# SIM808_RF.net
KiCad netlist of a schematic drawn in Altium Designer
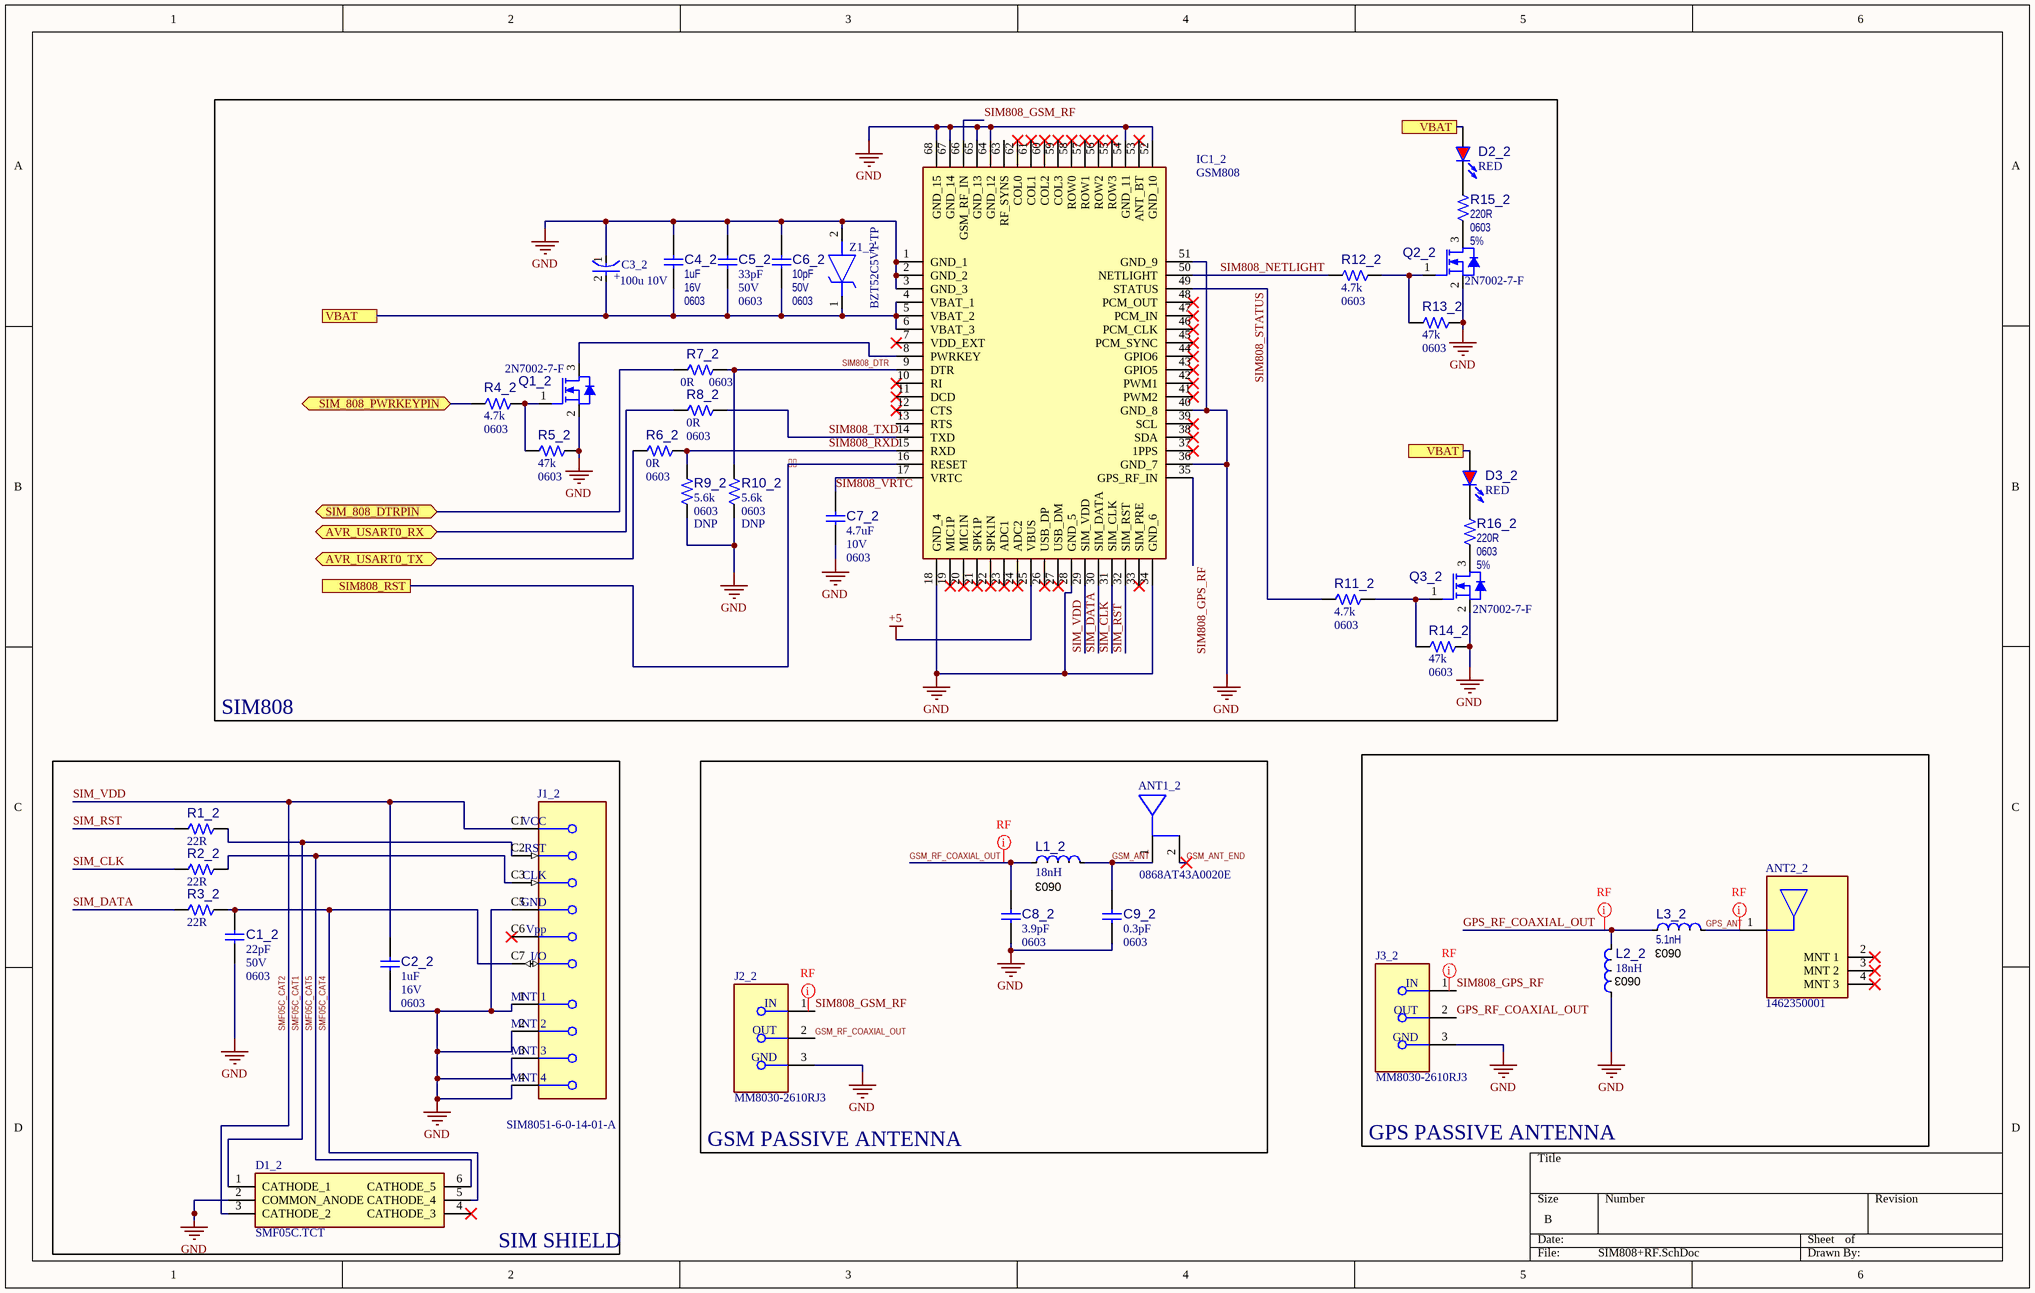
[diagram p0: SIM808+RF.SchDoc]

(export (version "E")
  (design (tool "Eeschema 10.0.6"))
  (components
    (comp (ref "ANT1_2")
      (value "0868AT43A0020E")
      (footprint "FP-0900AT43A0070E-MFG")
      (description "RF ANT CHIP SOLDER SMD")
      (libsource (lib "Altium Content Vault") (part "fdeedc8c81902f4dca238edc9264297"))
    )
    (comp (ref "ANT2_2")
      (value "1462350001")
      (footprint "FP-1462350001-MFG")
      (description "RF ANT 1.575GHZ MOLDED SLDR SMD")
      (fields
        (field (name "OCTOPART") "https://octopart.com/146235-0001-molex-75198029")
        (field (name "MANUFACTURER") "Molex")
      )
      (libsource (lib "Altium Content Vault") (part "44fa71a15c7cd8753818309cfbbf304"))
    )
    (comp (ref "C1_2")
      (value "22pF")
      (footprint "CAP_C_0603")
      (fields
        (field (name "VOLTAGE") "50V")
        (field (name "PACKAGE") "0603")
        (field (name "TOLERANCE") "5%")
        (field (name "Comment") "Capacitor NP")
      )
      (libsource (lib "MCHP-CDB") (part "Capacitor NP"))
    )
    (comp (ref "C2_2")
      (value "1uF")
      (footprint "CAP_C_0603")
      (fields
        (field (name "VOLTAGE") "16V")
        (field (name "PACKAGE") "0603")
        (field (name "TOLERANCE") "10%")
        (field (name "Comment") "Capacitor NP")
      )
      (libsource (lib "MCHP-CDB") (part "Capacitor NP"))
    )
    (comp (ref "C3_2")
      (value "100u 10V")
      (footprint "FP-TAJC-MFG")
      (description "100uF 10V  ±10% 1.2Ω 2312  SMD Tantalum Capacitor")
      (fields (field (name "TOLERANCE") "10%") (field (name "VOLTAGE") "10V"))
      (libsource (lib "Altium Content Vault") (part "203bc49f2ac43e59fd269a8c329ed05"))
    )
    (comp (ref "C4_2")
      (value "1uF")
      (footprint "CAP_C_0603")
      (fields
        (field (name "VOLTAGE") "16V")
        (field (name "PACKAGE") "0603")
        (field (name "TOLERANCE") "10%")
        (field (name "Comment") "Capacitor NP")
      )
      (libsource (lib "MCHP-CDB") (part "Capacitor NP"))
    )
    (comp (ref "C5_2")
      (value "33pF")
      (footprint "CAP_C_0603")
      (fields
        (field (name "VOLTAGE") "50V")
        (field (name "PACKAGE") "0603")
        (field (name "TOLERANCE") "5%")
        (field (name "Comment") "Capacitor NP")
      )
      (libsource (lib "MCHP-CDB") (part "Capacitor NP"))
    )
    (comp (ref "C6_2")
      (value "10pF")
      (footprint "CAP_C_0603")
      (fields
        (field (name "VOLTAGE") "50V")
        (field (name "PACKAGE") "0603")
        (field (name "TOLERANCE") "0.5pF")
        (field (name "Comment") "Capacitor NP")
        (field (name "OWNER") "Leah Whitaker")
      )
      (libsource (lib "MCHP-CDB") (part "Capacitor NP"))
    )
    (comp (ref "C7_2")
      (value "4.7uF")
      (footprint "CAP_C_0603")
      (fields
        (field (name "VOLTAGE") "10V")
        (field (name "PACKAGE") "0603")
        (field (name "TOLERANCE") "80%")
        (field (name "Comment") "Capacitor NP")
      )
      (libsource (lib "MCHP-CDB") (part "Capacitor NP"))
    )
    (comp (ref "C8_2")
      (value "3.9pF")
      (footprint "CAP_C_0603")
      (fields
        (field (name "PACKAGE") "0603")
        (field (name "TOLERANCE") "0.25pF")
        (field (name "Comment") "Capacitor NP")
      )
      (libsource (lib "MCHP-CDB") (part "Capacitor NP"))
    )
    (comp (ref "C9_2")
      (value "0.3pF")
      (footprint "CAP_C_0603")
      (fields
        (field (name "PACKAGE") "0603")
        (field (name "TOLERANCE") "0.25pF")
        (field (name "Comment") "Capacitor NP")
      )
      (libsource (lib "MCHP-CDB") (part "Capacitor NP"))
    )
    (comp (ref "D1_2")
      (value "SMF05C.TCT")
      (footprint "SamacSys:SOT65P210X110-6N")
      (description "TVS Diode (Uni-directional)")
      (fields (field (name "MOUSER PART NUMBER") "947-SMF05C.TCT"))
      (libsource (lib "*") (part "SMF05C.TCT"))
    )
    (comp (ref "D2_2")
      (value "RED")
      (footprint "LED_0603_RED")
      (description "LED")
      (fields (field (name "POWER") "100mW") (field (name "Comment") "LED_red"))
      (libsource (lib "MCHP-CDB") (part "LED_red"))
    )
    (comp (ref "D3_2")
      (value "RED")
      (footprint "LED_0603_RED")
      (description "LED")
      (fields (field (name "POWER") "100mW") (field (name "Comment") "LED_red"))
      (libsource (lib "MCHP-CDB") (part "LED_red"))
    )
    (comp (ref "IC1_2")
      (value "GSM808")
      (footprint "SamacSys:GSM808")
      (description "Integrated Circuit")
      (libsource (lib "*") (part "GSM808"))
    )
    (comp (ref "J1_2")
      (value "SIM8051-6-0-14-01-A")
      (footprint "FP-SIM8051-6-0-14-01-A-MFG")
      (description "NANO SIM PUSH PULL, 6P, SMT, 1.3")
      (fields
        (field (name "MANUFACTURER") "GCT")
        (field (name "OCTOPART") "https://octopart.com/sim8051-6-0-14-01-a-gct-99340323")
      )
      (libsource (lib "Altium Content Vault") (part "3cc3b1fb44b6b07564fa90550f448b7"))
    )
    (comp (ref "J2_2")
      (value "MM8030-2610RJ3")
      (footprint "FP-MM8030-2610RJ3-MFG")
      (description "CONN SWG RCPT STR 50 OHM SMD")
      (libsource (lib "Altium Content Vault") (part "d3d0eca1eedd57daa0a06598d6096e1"))
    )
    (comp (ref "J3_2")
      (value "MM8030-2610RJ3")
      (footprint "FP-MM8030-2610RJ3-MFG")
      (description "CONN SWG RCPT STR 50 OHM SMD")
      (libsource (lib "Altium Content Vault") (part "d3d0eca1eedd57daa0a06598d6096e1"))
    )
    (comp (ref "L1_2")
      (value "18nH")
      (footprint "IND_C_0603")
      (description "Inductor")
      (libsource (lib "MCHP-CDB") (part "Inductor"))
    )
    (comp (ref "L2_2")
      (value "18nH")
      (footprint "IND_C_0603")
      (description "Inductor")
      (libsource (lib "MCHP-CDB") (part "Inductor"))
    )
    (comp (ref "L3_2")
      (value "5.1nH")
      (footprint "IND_C_0603")
      (description "Inductor")
      (fields (field (name "OWNER") "Gabor Bihari"))
      (libsource (lib "MCHP-CDB") (part "Inductor"))
    )
    (comp (ref "Q1_2")
      (value "2N7002-7-F")
      (footprint "SOT-23-3")
      (description "Transistor MOS")
      (fields
        (field (name "POWER") "370mW")
        (field (name "Comment") "Transistor MOS-N GSD")
        (field (name "OWNER") "Adrian M (M91404)")
      )
      (libsource (lib "MCHP-CDB") (part "Transistor MOS-N GSD"))
    )
    (comp (ref "Q2_2")
      (value "2N7002-7-F")
      (footprint "SOT-23-3")
      (description "Transistor MOS")
      (fields
        (field (name "POWER") "370mW")
        (field (name "Comment") "Transistor MOS-N GSD")
        (field (name "OWNER") "Adrian M (M91404)")
      )
      (libsource (lib "MCHP-CDB") (part "Transistor MOS-N GSD"))
    )
    (comp (ref "Q3_2")
      (value "2N7002-7-F")
      (footprint "SOT-23-3")
      (description "Transistor MOS")
      (fields
        (field (name "POWER") "370mW")
        (field (name "Comment") "Transistor MOS-N GSD")
        (field (name "OWNER") "Adrian M (M91404)")
      )
      (libsource (lib "MCHP-CDB") (part "Transistor MOS-N GSD"))
    )
    (comp (ref "R1_2")
      (value "22R")
      (footprint "RES_C_0603")
      (description "Resistor")
      (fields (field (name "VOLTAGE") "75V") (field (name "POWER") "1/10W"))
      (libsource (lib "MCHP-CDB") (part "Resistor"))
    )
    (comp (ref "R2_2")
      (value "22R")
      (footprint "RES_C_0603")
      (description "Resistor")
      (fields (field (name "VOLTAGE") "75V") (field (name "POWER") "1/10W"))
      (libsource (lib "MCHP-CDB") (part "Resistor"))
    )
    (comp (ref "R3_2")
      (value "22R")
      (footprint "RES_C_0603")
      (description "Resistor")
      (fields (field (name "VOLTAGE") "75V") (field (name "POWER") "1/10W"))
      (libsource (lib "MCHP-CDB") (part "Resistor"))
    )
    (comp (ref "R4_2")
      (value "4.7k")
      (footprint "RES_C_0603")
      (description "Resistor")
      (fields
        (field (name "PACKAGE") "0603")
        (field (name "VOLTAGE") "75V")
        (field (name "POWER") "1/10W")
        (field (name "OWNER") "Bogdan P (M91398)")
      )
      (libsource (lib "MCHP-CDB") (part "Resistor"))
    )
    (comp (ref "R5_2")
      (value "47k")
      (footprint "RES_C_0603")
      (description "Resistor")
      (fields
        (field (name "PACKAGE") "0603")
        (field (name "VOLTAGE") "75V")
        (field (name "POWER") "1/10W")
        (field (name "OWNER") "Adrian M (M91404)")
      )
      (libsource (lib "MCHP-CDB") (part "Resistor"))
    )
    (comp (ref "R6_2")
      (value "0R")
      (footprint "RES_C_0603")
      (description "Resistor")
      (fields
        (field (name "PACKAGE") "0603")
        (field (name "POWER") "1/10W")
        (field (name "OWNER") "Steve Dziaba")
      )
      (libsource (lib "MCHP-CDB") (part "Resistor"))
    )
    (comp (ref "R7_2")
      (value "0R")
      (footprint "RES_C_0603")
      (description "Resistor")
      (fields
        (field (name "PACKAGE") "0603")
        (field (name "POWER") "1/10W")
        (field (name "OWNER") "Steve Dziaba")
      )
      (libsource (lib "MCHP-CDB") (part "Resistor"))
    )
    (comp (ref "R8_2")
      (value "0R")
      (footprint "RES_C_0603")
      (description "Resistor")
      (fields
        (field (name "PACKAGE") "0603")
        (field (name "POWER") "1/10W")
        (field (name "OWNER") "Steve Dziaba")
      )
      (libsource (lib "MCHP-CDB") (part "Resistor"))
    )
    (comp (ref "R9_2")
      (value "5.6k")
      (footprint "RES_C_0603")
      (description "Resistor")
      (fields
        (field (name "PACKAGE") "0603")
        (field (name "VOLTAGE") "50V")
        (field (name "POWER") "1/10W")
        (field (name "POPULATED") "DNP")
      )
      (libsource (lib "MCHP-CDB") (part "Resistor"))
    )
    (comp (ref "R10_2")
      (value "5.6k")
      (footprint "RES_C_0603")
      (description "Resistor")
      (fields
        (field (name "PACKAGE") "0603")
        (field (name "VOLTAGE") "50V")
        (field (name "POWER") "1/10W")
        (field (name "POPULATED") "DNP")
      )
      (libsource (lib "MCHP-CDB") (part "Resistor"))
    )
    (comp (ref "R11_2")
      (value "4.7k")
      (footprint "RES_C_0603")
      (description "Resistor")
      (fields
        (field (name "PACKAGE") "0603")
        (field (name "VOLTAGE") "75V")
        (field (name "POWER") "1/10W")
        (field (name "OWNER") "Bogdan P (M91398)")
      )
      (libsource (lib "MCHP-CDB") (part "Resistor"))
    )
    (comp (ref "R12_2")
      (value "4.7k")
      (footprint "RES_C_0603")
      (description "Resistor")
      (fields
        (field (name "PACKAGE") "0603")
        (field (name "VOLTAGE") "75V")
        (field (name "POWER") "1/10W")
        (field (name "OWNER") "Bogdan P (M91398)")
      )
      (libsource (lib "MCHP-CDB") (part "Resistor"))
    )
    (comp (ref "R13_2")
      (value "47k")
      (footprint "RES_C_0603")
      (description "Resistor")
      (fields
        (field (name "PACKAGE") "0603")
        (field (name "VOLTAGE") "75V")
        (field (name "POWER") "1/10W")
        (field (name "OWNER") "Adrian M (M91404)")
      )
      (libsource (lib "MCHP-CDB") (part "Resistor"))
    )
    (comp (ref "R14_2")
      (value "47k")
      (footprint "RES_C_0603")
      (description "Resistor")
      (fields
        (field (name "PACKAGE") "0603")
        (field (name "VOLTAGE") "75V")
        (field (name "POWER") "1/10W")
        (field (name "OWNER") "Adrian M (M91404)")
      )
      (libsource (lib "MCHP-CDB") (part "Resistor"))
    )
    (comp (ref "R15_2")
      (value "220R")
      (footprint "RES_C_0603")
      (description "Resistor")
      (fields
        (field (name "PACKAGE") "0603")
        (field (name "TOLERANCE") "5%")
        (field (name "VOLTAGE") "50V")
        (field (name "POWER") "1/10W")
      )
      (libsource (lib "MCHP-CDB") (part "Resistor"))
    )
    (comp (ref "R16_2")
      (value "220R")
      (footprint "RES_C_0603")
      (description "Resistor")
      (fields
        (field (name "PACKAGE") "0603")
        (field (name "TOLERANCE") "5%")
        (field (name "VOLTAGE") "50V")
        (field (name "POWER") "1/10W")
      )
      (libsource (lib "MCHP-CDB") (part "Resistor"))
    )
    (comp (ref "Z1_2")
      (value "BZT52C5V1-TP")
      (footprint "SamacSys:SOD3716X135N")
      (description "Zener Diode")
      (fields (field (name "MOUSER PART NUMBER") "833-BZT52C5V1-TP"))
      (libsource (lib "*") (part "BZT52C5V1-TP"))
    )
  )
  (nets
    (net (code "1") (name "+5") (class "Default")
      (node (ref "IC1_2") (pin "25") (pinfunction "VBUS_25") (pintype "passive"))
    )
    (net (code "2") (name "/") (class "Default")
      (node (ref "IC1_2") (pin "16") (pinfunction "RESET_16") (pintype "passive"))
    )
    (net (code "3") (name "/AVR_USART0_RX") (class "Default")
      (node (ref "R8_2") (pin "1") (pinfunction "1_1") (pintype "passive"))
    )
    (net (code "4") (name "/AVR_USART0_TX") (class "Default")
      (node (ref "R6_2") (pin "1") (pinfunction "1_1") (pintype "passive"))
    )
    (net (code "5") (name "/GPS_ANT") (class "Default")
      (node (ref "ANT2_2") (pin "1") (pinfunction "FEEDING_PAD_1") (pintype "passive"))
      (node (ref "L3_2") (pin "2") (pinfunction "F_2") (pintype "passive"))
    )
    (net (code "6") (name "/GPS_RF_COAXIAL_OUT") (class "Default")
      (node (ref "J3_2") (pin "2") (pinfunction "OUT_2") (pintype "passive"))
      (node (ref "L2_2") (pin "2") (pinfunction "F_2") (pintype "passive"))
      (node (ref "L3_2") (pin "1") (pinfunction "S_1") (pintype "passive"))
    )
    (net (code "7") (name "/GSM_ANT") (class "Default")
      (node (ref "ANT1_2") (pin "1") (pinfunction "RF_Feeding_Point_1") (pintype "passive"))
      (node (ref "C9_2") (pin "2") (pinfunction "2_2") (pintype "passive"))
      (node (ref "L1_2") (pin "2") (pinfunction "F_2") (pintype "passive"))
    )
    (net (code "8") (name "/GSM_ANT_END") (class "Default")
      (node (ref "ANT1_2") (pin "2") (pinfunction "To_trace_element_2") (pintype "passive+no_connect"))
    )
    (net (code "9") (name "/GSM_RF_COAXIAL_OUT") (class "Default")
      (node (ref "C8_2") (pin "2") (pinfunction "2_2") (pintype "passive"))
      (node (ref "J2_2") (pin "2") (pinfunction "OUT_2") (pintype "passive"))
      (node (ref "L1_2") (pin "1") (pinfunction "S_1") (pintype "passive"))
    )
    (net (code "10") (name "/SIM808_DTR") (class "Default")
      (node (ref "IC1_2") (pin "9") (pinfunction "DTR_9") (pintype "passive"))
      (node (ref "R10_2") (pin "2") (pinfunction "2_2") (pintype "passive"))
      (node (ref "R7_2") (pin "2") (pinfunction "2_2") (pintype "passive"))
    )
    (net (code "11") (name "/SIM808_GPS_RF") (class "Default")
      (node (ref "IC1_2") (pin "35") (pinfunction "GPS_RF_IN_35") (pintype "passive"))
      (node (ref "J3_2") (pin "1") (pinfunction "IN_1") (pintype "passive"))
    )
    (net (code "12") (name "/SIM808_GSM_RF") (class "Default")
      (node (ref "IC1_2") (pin "66") (pinfunction "GSM_RF_IN_66") (pintype "passive"))
      (node (ref "J2_2") (pin "1") (pinfunction "IN_1") (pintype "passive"))
    )
    (net (code "13") (name "/SIM808_NETLIGHT") (class "Default")
      (node (ref "IC1_2") (pin "50") (pinfunction "NETLIGHT_50") (pintype "passive"))
      (node (ref "R12_2") (pin "1") (pinfunction "1_1") (pintype "passive"))
    )
    (net (code "14") (name "/SIM808_RXD") (class "Default")
      (node (ref "IC1_2") (pin "15") (pinfunction "RXD_15") (pintype "passive"))
      (node (ref "R6_2") (pin "2") (pinfunction "2_2") (pintype "passive"))
      (node (ref "R9_2") (pin "2") (pinfunction "2_2") (pintype "passive"))
    )
    (net (code "15") (name "/SIM808_STATUS") (class "Default")
      (node (ref "IC1_2") (pin "49") (pinfunction "STATUS_49") (pintype "passive"))
      (node (ref "R11_2") (pin "1") (pinfunction "1_1") (pintype "passive"))
    )
    (net (code "16") (name "/SIM808_TXD") (class "Default")
      (node (ref "IC1_2") (pin "14") (pinfunction "TXD_14") (pintype "passive"))
      (node (ref "R8_2") (pin "2") (pinfunction "2_2") (pintype "passive"))
    )
    (net (code "17") (name "/SIM808_VRTC") (class "Default")
      (node (ref "C7_2") (pin "2") (pinfunction "2_2") (pintype "passive"))
      (node (ref "IC1_2") (pin "17") (pinfunction "VRTC_17") (pintype "passive"))
    )
    (net (code "18") (name "/SIM_808_DTRPIN") (class "Default")
      (node (ref "R7_2") (pin "1") (pinfunction "1_1") (pintype "passive"))
    )
    (net (code "19") (name "/SIM_808_PWRKEYPIN") (class "Default")
      (node (ref "R4_2") (pin "1") (pinfunction "1_1") (pintype "passive"))
    )
    (net (code "20") (name "/SIM_CLK") (class "Default")
      (node (ref "IC1_2") (pin "31") (pinfunction "SIM_CLK_31") (pintype "passive"))
      (node (ref "R2_2") (pin "1") (pinfunction "1_1") (pintype "passive"))
    )
    (net (code "21") (name "/SIM_DATA") (class "Default")
      (node (ref "IC1_2") (pin "30") (pinfunction "SIM_DATA_30") (pintype "passive"))
      (node (ref "R3_2") (pin "1") (pinfunction "1_1") (pintype "passive"))
    )
    (net (code "22") (name "/SIM_RST") (class "Default")
      (node (ref "IC1_2") (pin "32") (pinfunction "SIM_RST_32") (pintype "passive"))
      (node (ref "R1_2") (pin "1") (pinfunction "1_1") (pintype "passive"))
    )
    (net (code "23") (name "/SIM_VDD") (class "Default")
      (node (ref "C2_2") (pin "2") (pinfunction "2_2") (pintype "passive"))
      (node (ref "D1_2") (pin "3") (pinfunction "CATHODE_2_3") (pintype "passive"))
      (node (ref "IC1_2") (pin "29") (pinfunction "SIM_VDD_29") (pintype "passive"))
      (node (ref "J1_2") (pin "C1") (pinfunction "VCC_C1") (pintype "power_in"))
    )
    (net (code "24") (name "/SMF05C_CAT1") (class "Default")
      (node (ref "D1_2") (pin "1") (pinfunction "CATHODE_1_1") (pintype "passive"))
      (node (ref "J1_2") (pin "C2") (pinfunction "RST_C2") (pintype "input"))
      (node (ref "R1_2") (pin "2") (pinfunction "2_2") (pintype "passive"))
    )
    (net (code "25") (name "/SMF05C_CAT4") (class "Default")
      (node (ref "C1_2") (pin "2") (pinfunction "2_2") (pintype "passive"))
      (node (ref "D1_2") (pin "5") (pinfunction "CATHODE_4_5") (pintype "passive"))
      (node (ref "J1_2") (pin "C7") (pinfunction "I/O_C7") (pintype "bidirectional"))
      (node (ref "R3_2") (pin "2") (pinfunction "2_2") (pintype "passive"))
    )
    (net (code "26") (name "/SMF05C_CAT5") (class "Default")
      (node (ref "D1_2") (pin "6") (pinfunction "CATHODE_5_6") (pintype "passive"))
      (node (ref "J1_2") (pin "C3") (pinfunction "CLK_C3") (pintype "input"))
      (node (ref "R2_2") (pin "2") (pinfunction "2_2") (pintype "passive"))
    )
    (net (code "27") (name "/VBAT") (class "Default")
      (node (ref "C3_2") (pin "2") (pinfunction "A_2") (pintype "passive"))
      (node (ref "C4_2") (pin "1") (pinfunction "1_1") (pintype "passive"))
      (node (ref "C5_2") (pin "2") (pinfunction "2_2") (pintype "passive"))
      (node (ref "C6_2") (pin "1") (pinfunction "1_1") (pintype "passive"))
      (node (ref "D2_2") (pin "1") (pinfunction "A_1") (pintype "passive"))
      (node (ref "D3_2") (pin "1") (pinfunction "A_1") (pintype "passive"))
      (node (ref "IC1_2") (pin "4") (pinfunction "VBAT_1_4") (pintype "passive"))
      (node (ref "IC1_2") (pin "5") (pinfunction "VBAT_2_5") (pintype "passive"))
      (node (ref "IC1_2") (pin "6") (pinfunction "VBAT_3_6") (pintype "passive"))
      (node (ref "Z1_2") (pin "1") (pinfunction "K_1") (pintype "passive"))
    )
    (net (code "28") (name "GND") (class "Default")
      (node (ref "C1_2") (pin "1") (pinfunction "1_1") (pintype "passive"))
      (node (ref "C2_2") (pin "1") (pinfunction "1_1") (pintype "passive"))
      (node (ref "C3_2") (pin "1") (pinfunction "C_1") (pintype "passive"))
      (node (ref "C4_2") (pin "2") (pinfunction "2_2") (pintype "passive"))
      (node (ref "C5_2") (pin "1") (pinfunction "1_1") (pintype "passive"))
      (node (ref "C6_2") (pin "2") (pinfunction "2_2") (pintype "passive"))
      (node (ref "C7_2") (pin "1") (pinfunction "1_1") (pintype "passive"))
      (node (ref "C8_2") (pin "1") (pinfunction "1_1") (pintype "passive"))
      (node (ref "C9_2") (pin "1") (pinfunction "1_1") (pintype "passive"))
      (node (ref "D1_2") (pin "2") (pinfunction "COMMON_ANODE_2") (pintype "passive"))
      (node (ref "IC1_2") (pin "1") (pinfunction "GND_1_1") (pintype "passive"))
      (node (ref "IC1_2") (pin "18") (pinfunction "GND_4_18") (pintype "passive"))
      (node (ref "IC1_2") (pin "2") (pinfunction "GND_2_2") (pintype "passive"))
      (node (ref "IC1_2") (pin "28") (pinfunction "GND_5_28") (pintype "passive"))
      (node (ref "IC1_2") (pin "3") (pinfunction "GND_3_3") (pintype "passive"))
      (node (ref "IC1_2") (pin "34") (pinfunction "GND_6_34") (pintype "passive"))
      (node (ref "IC1_2") (pin "36") (pinfunction "GND_7_36") (pintype "passive"))
      (node (ref "IC1_2") (pin "40") (pinfunction "GND_8_40") (pintype "passive"))
      (node (ref "IC1_2") (pin "51") (pinfunction "GND_9_51") (pintype "passive"))
      (node (ref "IC1_2") (pin "52") (pinfunction "GND_10_52") (pintype "passive"))
      (node (ref "IC1_2") (pin "54") (pinfunction "GND_11_54") (pintype "passive"))
      (node (ref "IC1_2") (pin "64") (pinfunction "GND_12_64") (pintype "passive"))
      (node (ref "IC1_2") (pin "65") (pinfunction "GND_13_65") (pintype "passive"))
      (node (ref "IC1_2") (pin "67") (pinfunction "GND_14_67") (pintype "passive"))
      (node (ref "IC1_2") (pin "68") (pinfunction "GND_15_68") (pintype "passive"))
      (node (ref "J1_2") (pin "1") (pinfunction "MNT_1_1") (pintype "passive"))
      (node (ref "J1_2") (pin "2") (pinfunction "MNT_2_2") (pintype "passive"))
      (node (ref "J1_2") (pin "3") (pinfunction "MNT_3_3") (pintype "passive"))
      (node (ref "J1_2") (pin "4") (pinfunction "MNT_4_4") (pintype "passive"))
      (node (ref "J1_2") (pin "C5") (pinfunction "GND_C5") (pintype "power_in"))
      (node (ref "J2_2") (pin "3") (pinfunction "GND_3") (pintype "passive"))
      (node (ref "J3_2") (pin "3") (pinfunction "GND_3") (pintype "passive"))
      (node (ref "L2_2") (pin "1") (pinfunction "S_1") (pintype "passive"))
      (node (ref "Q1_2") (pin "2") (pinfunction "S_2") (pintype "passive"))
      (node (ref "Q2_2") (pin "2") (pinfunction "S_2") (pintype "passive"))
      (node (ref "Q3_2") (pin "2") (pinfunction "S_2") (pintype "passive"))
      (node (ref "R10_2") (pin "1") (pinfunction "1_1") (pintype "passive"))
      (node (ref "R13_2") (pin "2") (pinfunction "2_2") (pintype "passive"))
      (node (ref "R14_2") (pin "2") (pinfunction "2_2") (pintype "passive"))
      (node (ref "R5_2") (pin "2") (pinfunction "2_2") (pintype "passive"))
      (node (ref "R9_2") (pin "1") (pinfunction "1_1") (pintype "passive"))
      (node (ref "Z1_2") (pin "2") (pinfunction "A_2") (pintype "passive"))
    )
    (net (code "29") (name "Net-(D2_2-K)") (class "Default")
      (node (ref "D2_2") (pin "2") (pinfunction "K_2") (pintype "passive"))
      (node (ref "R15_2") (pin "2") (pinfunction "2_2") (pintype "passive"))
    )
    (net (code "30") (name "Net-(D3_2-K)") (class "Default")
      (node (ref "D3_2") (pin "2") (pinfunction "K_2") (pintype "passive"))
      (node (ref "R16_2") (pin "2") (pinfunction "2_2") (pintype "passive"))
    )
    (net (code "31") (name "Net-(IC1_2-PWRKEY)") (class "Default")
      (node (ref "IC1_2") (pin "8") (pinfunction "PWRKEY_8") (pintype "passive"))
      (node (ref "Q1_2") (pin "3") (pinfunction "D_3") (pintype "passive"))
    )
    (net (code "32") (name "Net-(Q1_2-G)") (class "Default")
      (node (ref "Q1_2") (pin "1") (pinfunction "G_1") (pintype "passive"))
      (node (ref "R4_2") (pin "2") (pinfunction "2_2") (pintype "passive"))
      (node (ref "R5_2") (pin "1") (pinfunction "1_1") (pintype "passive"))
    )
    (net (code "33") (name "Net-(Q2_2-D)") (class "Default")
      (node (ref "Q2_2") (pin "3") (pinfunction "D_3") (pintype "passive"))
      (node (ref "R15_2") (pin "1") (pinfunction "1_1") (pintype "passive"))
    )
    (net (code "34") (name "Net-(Q2_2-G)") (class "Default")
      (node (ref "Q2_2") (pin "1") (pinfunction "G_1") (pintype "passive"))
      (node (ref "R12_2") (pin "2") (pinfunction "2_2") (pintype "passive"))
      (node (ref "R13_2") (pin "1") (pinfunction "1_1") (pintype "passive"))
    )
    (net (code "35") (name "Net-(Q3_2-D)") (class "Default")
      (node (ref "Q3_2") (pin "3") (pinfunction "D_3") (pintype "passive"))
      (node (ref "R16_2") (pin "1") (pinfunction "1_1") (pintype "passive"))
    )
    (net (code "36") (name "Net-(Q3_2-G)") (class "Default")
      (node (ref "Q3_2") (pin "1") (pinfunction "G_1") (pintype "passive"))
      (node (ref "R11_2") (pin "2") (pinfunction "2_2") (pintype "passive"))
      (node (ref "R14_2") (pin "1") (pinfunction "1_1") (pintype "passive"))
    )
    (net (code "37") (name "unconnected-(ANT2_2-MNT_1-Pad2)") (class "Default")
      (node (ref "ANT2_2") (pin "2") (pinfunction "MNT_1_2") (pintype "passive+no_connect"))
    )
    (net (code "38") (name "unconnected-(ANT2_2-MNT_2-Pad3)") (class "Default")
      (node (ref "ANT2_2") (pin "3") (pinfunction "MNT_2_3") (pintype "passive+no_connect"))
    )
    (net (code "39") (name "unconnected-(ANT2_2-MNT_3-Pad4)") (class "Default")
      (node (ref "ANT2_2") (pin "4") (pinfunction "MNT_3_4") (pintype "passive+no_connect"))
    )
    (net (code "40") (name "unconnected-(D1_2-CATHODE_3-Pad4)") (class "Default")
      (node (ref "D1_2") (pin "4") (pinfunction "CATHODE_3_4") (pintype "passive+no_connect"))
    )
    (net (code "41") (name "unconnected-(IC1_2-1PPS-Pad37)") (class "Default")
      (node (ref "IC1_2") (pin "37") (pinfunction "1PPS_37") (pintype "passive+no_connect"))
    )
    (net (code "42") (name "unconnected-(IC1_2-ADC1-Pad23)") (class "Default")
      (node (ref "IC1_2") (pin "23") (pinfunction "ADC1_23") (pintype "passive+no_connect"))
    )
    (net (code "43") (name "unconnected-(IC1_2-ADC2-Pad24)") (class "Default")
      (node (ref "IC1_2") (pin "24") (pinfunction "ADC2_24") (pintype "passive+no_connect"))
    )
    (net (code "44") (name "unconnected-(IC1_2-ANT_BT-Pad53)") (class "Default")
      (node (ref "IC1_2") (pin "53") (pinfunction "ANT_BT_53") (pintype "passive+no_connect"))
    )
    (net (code "45") (name "unconnected-(IC1_2-COL0-Pad62)") (class "Default")
      (node (ref "IC1_2") (pin "62") (pinfunction "COL0_62") (pintype "passive+no_connect"))
    )
    (net (code "46") (name "unconnected-(IC1_2-COL1-Pad61)") (class "Default")
      (node (ref "IC1_2") (pin "61") (pinfunction "COL1_61") (pintype "passive+no_connect"))
    )
    (net (code "47") (name "unconnected-(IC1_2-COL2-Pad60)") (class "Default")
      (node (ref "IC1_2") (pin "60") (pinfunction "COL2_60") (pintype "passive+no_connect"))
    )
    (net (code "48") (name "unconnected-(IC1_2-COL3-Pad59)") (class "Default")
      (node (ref "IC1_2") (pin "59") (pinfunction "COL3_59") (pintype "passive+no_connect"))
    )
    (net (code "49") (name "unconnected-(IC1_2-CTS-Pad12)") (class "Default")
      (node (ref "IC1_2") (pin "12") (pinfunction "CTS_12") (pintype "passive+no_connect"))
    )
    (net (code "50") (name "unconnected-(IC1_2-DCD-Pad11)") (class "Default")
      (node (ref "IC1_2") (pin "11") (pinfunction "DCD_11") (pintype "passive+no_connect"))
    )
    (net (code "51") (name "unconnected-(IC1_2-GPIO5-Pad43)") (class "Default")
      (node (ref "IC1_2") (pin "43") (pinfunction "GPIO5_43") (pintype "passive+no_connect"))
    )
    (net (code "52") (name "unconnected-(IC1_2-GPIO6-Pad44)") (class "Default")
      (node (ref "IC1_2") (pin "44") (pinfunction "GPIO6_44") (pintype "passive+no_connect"))
    )
    (net (code "53") (name "unconnected-(IC1_2-MIC1N-Pad20)") (class "Default")
      (node (ref "IC1_2") (pin "20") (pinfunction "MIC1N_20") (pintype "passive+no_connect"))
    )
    (net (code "54") (name "unconnected-(IC1_2-MIC1P-Pad19)") (class "Default")
      (node (ref "IC1_2") (pin "19") (pinfunction "MIC1P_19") (pintype "passive+no_connect"))
    )
    (net (code "55") (name "unconnected-(IC1_2-PCM_CLK-Pad46)") (class "Default")
      (node (ref "IC1_2") (pin "46") (pinfunction "PCM_CLK_46") (pintype "passive+no_connect"))
    )
    (net (code "56") (name "unconnected-(IC1_2-PCM_IN-Pad47)") (class "Default")
      (node (ref "IC1_2") (pin "47") (pinfunction "PCM_IN_47") (pintype "passive+no_connect"))
    )
    (net (code "57") (name "unconnected-(IC1_2-PCM_OUT-Pad48)") (class "Default")
      (node (ref "IC1_2") (pin "48") (pinfunction "PCM_OUT_48") (pintype "passive+no_connect"))
    )
    (net (code "58") (name "unconnected-(IC1_2-PCM_SYNC-Pad45)") (class "Default")
      (node (ref "IC1_2") (pin "45") (pinfunction "PCM_SYNC_45") (pintype "passive+no_connect"))
    )
    (net (code "59") (name "unconnected-(IC1_2-PWM1-Pad42)") (class "Default")
      (node (ref "IC1_2") (pin "42") (pinfunction "PWM1_42") (pintype "passive+no_connect"))
    )
    (net (code "60") (name "unconnected-(IC1_2-PWM2-Pad41)") (class "Default")
      (node (ref "IC1_2") (pin "41") (pinfunction "PWM2_41") (pintype "passive+no_connect"))
    )
    (net (code "61") (name "unconnected-(IC1_2-RF_SYNS-Pad63)") (class "Default")
      (node (ref "IC1_2") (pin "63") (pinfunction "RF_SYNS_63") (pintype "passive"))
    )
    (net (code "62") (name "unconnected-(IC1_2-RI-Pad10)") (class "Default")
      (node (ref "IC1_2") (pin "10") (pinfunction "RI_10") (pintype "passive+no_connect"))
    )
    (net (code "63") (name "unconnected-(IC1_2-ROW0-Pad58)") (class "Default")
      (node (ref "IC1_2") (pin "58") (pinfunction "ROW0_58") (pintype "passive+no_connect"))
    )
    (net (code "64") (name "unconnected-(IC1_2-ROW1-Pad57)") (class "Default")
      (node (ref "IC1_2") (pin "57") (pinfunction "ROW1_57") (pintype "passive+no_connect"))
    )
    (net (code "65") (name "unconnected-(IC1_2-ROW2-Pad56)") (class "Default")
      (node (ref "IC1_2") (pin "56") (pinfunction "ROW2_56") (pintype "passive+no_connect"))
    )
    (net (code "66") (name "unconnected-(IC1_2-ROW3-Pad55)") (class "Default")
      (node (ref "IC1_2") (pin "55") (pinfunction "ROW3_55") (pintype "passive+no_connect"))
    )
    (net (code "67") (name "unconnected-(IC1_2-RTS-Pad13)") (class "Default")
      (node (ref "IC1_2") (pin "13") (pinfunction "RTS_13") (pintype "passive"))
    )
    (net (code "68") (name "unconnected-(IC1_2-SCL-Pad39)") (class "Default")
      (node (ref "IC1_2") (pin "39") (pinfunction "SCL_39") (pintype "passive+no_connect"))
    )
    (net (code "69") (name "unconnected-(IC1_2-SDA-Pad38)") (class "Default")
      (node (ref "IC1_2") (pin "38") (pinfunction "SDA_38") (pintype "passive+no_connect"))
    )
    (net (code "70") (name "unconnected-(IC1_2-SIM_PRE-Pad33)") (class "Default")
      (node (ref "IC1_2") (pin "33") (pinfunction "SIM_PRE_33") (pintype "passive+no_connect"))
    )
    (net (code "71") (name "unconnected-(IC1_2-SPK1N-Pad22)") (class "Default")
      (node (ref "IC1_2") (pin "22") (pinfunction "SPK1N_22") (pintype "passive+no_connect"))
    )
    (net (code "72") (name "unconnected-(IC1_2-SPK1P-Pad21)") (class "Default")
      (node (ref "IC1_2") (pin "21") (pinfunction "SPK1P_21") (pintype "passive+no_connect"))
    )
    (net (code "73") (name "unconnected-(IC1_2-USB_DM-Pad27)") (class "Default")
      (node (ref "IC1_2") (pin "27") (pinfunction "USB_DM_27") (pintype "passive+no_connect"))
    )
    (net (code "74") (name "unconnected-(IC1_2-USB_DP-Pad26)") (class "Default")
      (node (ref "IC1_2") (pin "26") (pinfunction "USB_DP_26") (pintype "passive+no_connect"))
    )
    (net (code "75") (name "unconnected-(IC1_2-VDD_EXT-Pad7)") (class "Default")
      (node (ref "IC1_2") (pin "7") (pinfunction "VDD_EXT_7") (pintype "passive+no_connect"))
    )
    (net (code "76") (name "unconnected-(J1_2-Vpp-PadC6)") (class "Default")
      (node (ref "J1_2") (pin "C6") (pinfunction "Vpp_C6") (pintype "power_in+no_connect"))
    )
  )
)
